# IRIS.net
KiCad netlist of a schematic drawn in EAGLE
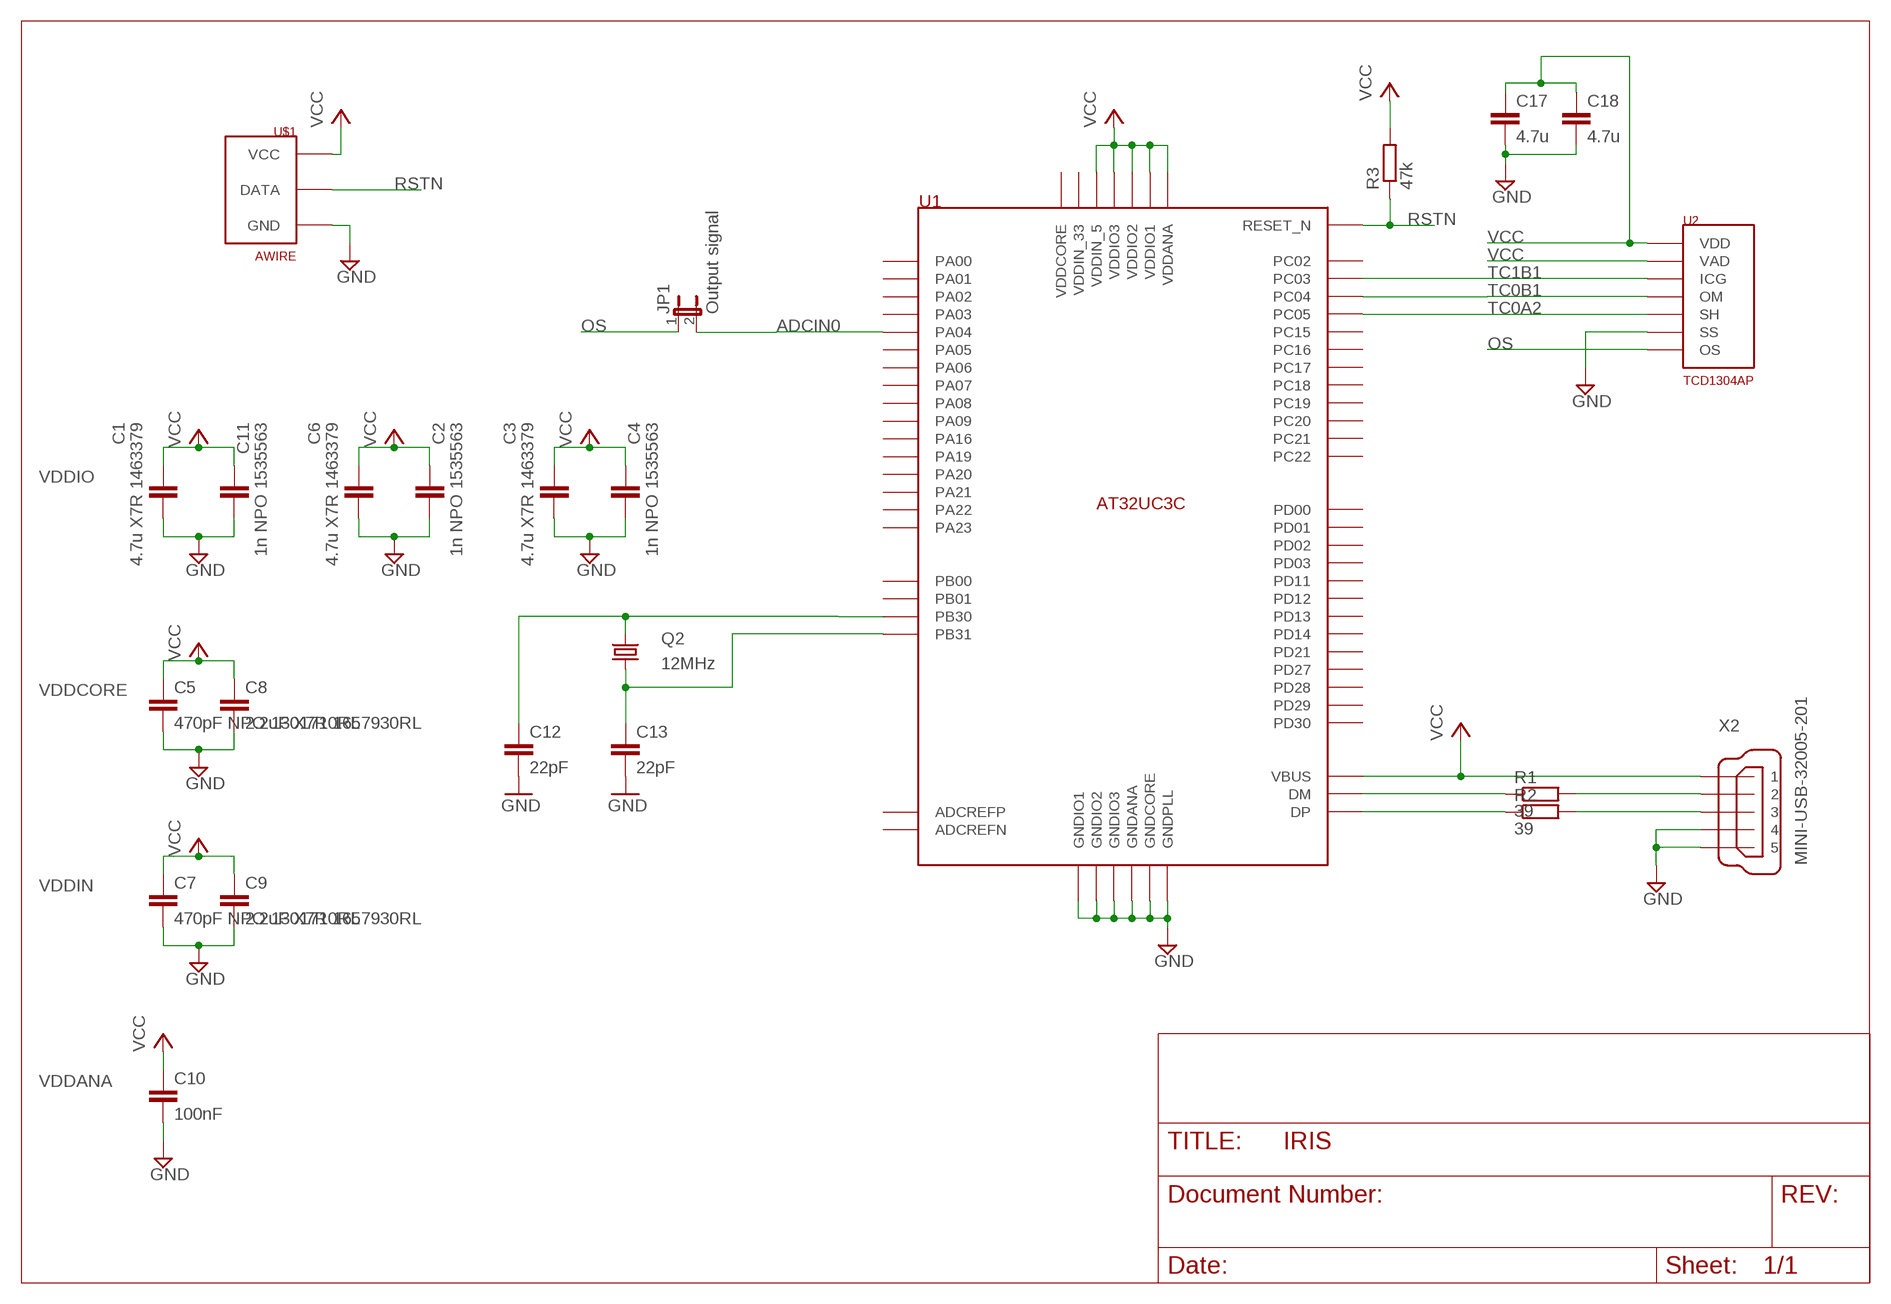
[diagram p0: schematic, sheet 1]

(export (version "E")
  (design (tool "Eeschema 10.0.6"))
  (components
    (comp (ref "C1")
      (value "4.7u X7R 1463379")
      (footprint "eagle-import:C0603")
      (libsource (lib "eagle-import") (part "C-EUC0603"))
    )
    (comp (ref "C2")
      (value "1n NPO 1535563")
      (footprint "eagle-import:C0402")
      (libsource (lib "eagle-import") (part "C-EUC0402"))
    )
    (comp (ref "C3")
      (value "4.7u X7R 1463379")
      (footprint "eagle-import:C0603")
      (libsource (lib "eagle-import") (part "C-EUC0603"))
    )
    (comp (ref "C4")
      (value "1n NPO 1535563")
      (footprint "eagle-import:C0402")
      (libsource (lib "eagle-import") (part "C-EUC0402"))
    )
    (comp (ref "C5")
      (value "470pF NPO 1301710RL")
      (footprint "eagle-import:C0603")
      (libsource (lib "eagle-import") (part "C-EUC0603"))
    )
    (comp (ref "C6")
      (value "4.7u X7R 1463379")
      (footprint "eagle-import:C0603")
      (libsource (lib "eagle-import") (part "C-EUC0603"))
    )
    (comp (ref "C7")
      (value "470pF NPO 1301710RL")
      (footprint "eagle-import:C0603")
      (libsource (lib "eagle-import") (part "C-EUC0603"))
    )
    (comp (ref "C8")
      (value "2.2uF X7R 1657930RL")
      (footprint "eagle-import:C0603")
      (libsource (lib "eagle-import") (part "C-EUC0603"))
    )
    (comp (ref "C9")
      (value "2.2uF X7R 1657930RL")
      (footprint "eagle-import:C0603")
      (libsource (lib "eagle-import") (part "C-EUC0603"))
    )
    (comp (ref "C10")
      (value "100nF")
      (footprint "eagle-import:C0603")
      (libsource (lib "eagle-import") (part "C-EUC0603"))
    )
    (comp (ref "C11")
      (value "1n NPO 1535563")
      (footprint "eagle-import:C0402")
      (libsource (lib "eagle-import") (part "C-EUC0402"))
    )
    (comp (ref "C12")
      (value "22pF")
      (footprint "eagle-import:C0402")
      (libsource (lib "eagle-import") (part "C-EUC0402"))
    )
    (comp (ref "C13")
      (value "22pF")
      (footprint "eagle-import:C0402")
      (libsource (lib "eagle-import") (part "C-EUC0402"))
    )
    (comp (ref "C17")
      (value "4.7u")
      (footprint "eagle-import:C0805")
      (libsource (lib "eagle-import") (part "resistor_C-EUC0805"))
    )
    (comp (ref "C18")
      (value "4.7u")
      (footprint "eagle-import:C0805")
      (libsource (lib "eagle-import") (part "resistor_C-EUC0805"))
    )
    (comp (ref "JP1")
      (value "Output signal")
      (footprint "eagle-import:JP1")
      (libsource (lib "eagle-import") (part "JP1E"))
    )
    (comp (ref "Q2")
      (value "12MHz")
      (footprint "eagle-import:CRYSTAL-SMD-5X3")
      (libsource (lib "eagle-import") (part "CRYSTAL5X3"))
    )
    (comp (ref "R1")
      (value "39")
      (footprint "eagle-import:R0603")
      (libsource (lib "eagle-import") (part "R-EU_R0603"))
    )
    (comp (ref "R2")
      (value "39")
      (footprint "eagle-import:R0603")
      (libsource (lib "eagle-import") (part "R-EU_R0603"))
    )
    (comp (ref "R3")
      (value "47k")
      (footprint "eagle-import:R0603")
      (libsource (lib "eagle-import") (part "R-EU_R0603"))
    )
    (comp (ref "U$1")
      (value "AWIRE")
      (footprint "eagle-import:AWIRE")
      (libsource (lib "eagle-import") (part "AWIRE"))
    )
    (comp (ref "U1")
      (value "AT32UC3C")
      (footprint "eagle-import:TQFP64")
      (libsource (lib "eagle-import") (part "AT32UC3C"))
    )
    (comp (ref "U2")
      (value "TCD1304AP")
      (footprint "eagle-import:TCD1304AP")
      (libsource (lib "eagle-import") (part "TCD1304AP"))
    )
    (comp (ref "X2")
      (value "MINI-USB-32005-201")
      (footprint "eagle-import:32005-201")
      (libsource (lib "eagle-import") (part "MINI-USB-32005-201"))
    )
  )
  (nets
    (net (code "1") (name "/ADCIN0") (class "Default")
      (node (ref "JP1") (pin "2") (pinfunction "2_2") (pintype "passive"))
      (node (ref "U1") (pin "P$7") (pinfunction "PA04_P$7") (pintype "bidirectional"))
    )
    (net (code "2") (name "/OS") (class "Default")
      (node (ref "JP1") (pin "1") (pinfunction "1_1") (pintype "passive"))
      (node (ref "U2") (pin "P$21") (pinfunction "OS_P$21") (pintype "bidirectional"))
    )
    (net (code "3") (name "/RSTN") (class "Default")
      (node (ref "R3") (pin "1") (pinfunction "1_1") (pintype "passive"))
      (node (ref "U$1") (pin "P$2") (pinfunction "DATA_P$2") (pintype "bidirectional"))
      (node (ref "U1") (pin "P$64") (pinfunction "RESET_N_P$64") (pintype "bidirectional"))
    )
    (net (code "4") (name "/TC0A2") (class "Default")
      (node (ref "U1") (pin "P$38") (pinfunction "PC05_P$38") (pintype "bidirectional"))
      (node (ref "U2") (pin "P$5") (pinfunction "SH_P$5") (pintype "bidirectional"))
    )
    (net (code "5") (name "/TC0B1") (class "Default")
      (node (ref "U1") (pin "P$37") (pinfunction "PC04_P$37") (pintype "bidirectional"))
      (node (ref "U2") (pin "P$4") (pinfunction "OM_P$4") (pintype "bidirectional"))
    )
    (net (code "6") (name "/TC1B1") (class "Default")
      (node (ref "U1") (pin "P$34") (pinfunction "PC03_P$34") (pintype "bidirectional"))
      (node (ref "U2") (pin "P$3") (pinfunction "ICG_P$3") (pintype "bidirectional"))
    )
    (net (code "7") (name "GND") (class "Default")
      (node (ref "C1") (pin "2") (pinfunction "2_2") (pintype "passive"))
      (node (ref "C10") (pin "2") (pinfunction "2_2") (pintype "passive"))
      (node (ref "C11") (pin "2") (pinfunction "2_2") (pintype "passive"))
      (node (ref "C12") (pin "2") (pinfunction "2_2") (pintype "passive"))
      (node (ref "C13") (pin "2") (pinfunction "2_2") (pintype "passive"))
      (node (ref "C17") (pin "2") (pinfunction "2_2") (pintype "passive"))
      (node (ref "C18") (pin "2") (pinfunction "2_2") (pintype "passive"))
      (node (ref "C2") (pin "2") (pinfunction "2_2") (pintype "passive"))
      (node (ref "C3") (pin "2") (pinfunction "2_2") (pintype "passive"))
      (node (ref "C4") (pin "2") (pinfunction "2_2") (pintype "passive"))
      (node (ref "C5") (pin "2") (pinfunction "2_2") (pintype "passive"))
      (node (ref "C6") (pin "2") (pinfunction "2_2") (pintype "passive"))
      (node (ref "C7") (pin "2") (pinfunction "2_2") (pintype "passive"))
      (node (ref "C8") (pin "2") (pinfunction "2_2") (pintype "passive"))
      (node (ref "C9") (pin "2") (pinfunction "2_2") (pintype "passive"))
      (node (ref "U$1") (pin "P$3") (pinfunction "GND_P$3") (pintype "bidirectional"))
      (node (ref "U1") (pin "P$17") (pinfunction "GNDANA_P$17") (pintype "bidirectional"))
      (node (ref "U1") (pin "P$26") (pinfunction "GNDPLL_P$26") (pintype "bidirectional"))
      (node (ref "U1") (pin "P$30") (pinfunction "GNDCORE_P$30") (pintype "bidirectional"))
      (node (ref "U1") (pin "P$36") (pinfunction "GNDIO2_P$36") (pintype "bidirectional"))
      (node (ref "U1") (pin "P$52") (pinfunction "GNDIO3_P$52") (pintype "bidirectional"))
      (node (ref "U1") (pin "P$6") (pinfunction "GNDIO1_P$6") (pintype "bidirectional"))
      (node (ref "U2") (pin "P$22") (pinfunction "SS_P$22") (pintype "bidirectional"))
      (node (ref "X2") (pin "4") (pinfunction "4_4") (pintype "passive"))
      (node (ref "X2") (pin "5") (pinfunction "5_5") (pintype "passive"))
    )
    (net (code "8") (name "Net-(Q2-2)") (class "Default")
      (node (ref "C12") (pin "1") (pinfunction "1_1") (pintype "passive"))
      (node (ref "Q2") (pin "3") (pinfunction "2_3") (pintype "passive"))
      (node (ref "U1") (pin "P$31") (pinfunction "PB30_P$31") (pintype "bidirectional"))
    )
    (net (code "9") (name "Net-(R1-Pad2)") (class "Default")
      (node (ref "R1") (pin "2") (pinfunction "2_2") (pintype "passive"))
      (node (ref "X2") (pin "2") (pinfunction "2_2") (pintype "passive"))
    )
    (net (code "10") (name "Net-(R2-Pad2)") (class "Default")
      (node (ref "R2") (pin "2") (pinfunction "2_2") (pintype "passive"))
      (node (ref "X2") (pin "3") (pinfunction "3_3") (pintype "passive"))
    )
    (net (code "11") (name "Net-(U1-DM)") (class "Default")
      (node (ref "R1") (pin "1") (pinfunction "1_1") (pintype "passive"))
      (node (ref "U1") (pin "P$24") (pinfunction "DM_P$24") (pintype "bidirectional"))
    )
    (net (code "12") (name "Net-(U1-DP)") (class "Default")
      (node (ref "R2") (pin "1") (pinfunction "1_1") (pintype "passive"))
      (node (ref "U1") (pin "P$25") (pinfunction "DP_P$25") (pintype "bidirectional"))
    )
    (net (code "13") (name "Net-(U1-PB31)") (class "Default")
      (node (ref "C13") (pin "1") (pinfunction "1_1") (pintype "passive"))
      (node (ref "Q2") (pin "1") (pinfunction "1_1") (pintype "passive"))
      (node (ref "U1") (pin "P$32") (pinfunction "PB31_P$32") (pintype "bidirectional"))
    )
    (net (code "14") (name "VCC") (class "Default")
      (node (ref "C1") (pin "1") (pinfunction "1_1") (pintype "passive"))
      (node (ref "C10") (pin "1") (pinfunction "1_1") (pintype "passive"))
      (node (ref "C11") (pin "1") (pinfunction "1_1") (pintype "passive"))
      (node (ref "C17") (pin "1") (pinfunction "1_1") (pintype "passive"))
      (node (ref "C18") (pin "1") (pinfunction "1_1") (pintype "passive"))
      (node (ref "C2") (pin "1") (pinfunction "1_1") (pintype "passive"))
      (node (ref "C3") (pin "1") (pinfunction "1_1") (pintype "passive"))
      (node (ref "C4") (pin "1") (pinfunction "1_1") (pintype "passive"))
      (node (ref "C5") (pin "1") (pinfunction "1_1") (pintype "passive"))
      (node (ref "C6") (pin "1") (pinfunction "1_1") (pintype "passive"))
      (node (ref "C7") (pin "1") (pinfunction "1_1") (pintype "passive"))
      (node (ref "C8") (pin "1") (pinfunction "1_1") (pintype "passive"))
      (node (ref "C9") (pin "1") (pinfunction "1_1") (pintype "passive"))
      (node (ref "R3") (pin "2") (pinfunction "2_2") (pintype "passive"))
      (node (ref "U$1") (pin "P$1") (pinfunction "VCC_P$1") (pintype "bidirectional"))
      (node (ref "U1") (pin "P$18") (pinfunction "VDDANA_P$18") (pintype "bidirectional"))
      (node (ref "U1") (pin "P$23") (pinfunction "VBUS_P$23") (pintype "bidirectional"))
      (node (ref "U1") (pin "P$27") (pinfunction "VDDIN_5_P$27") (pintype "bidirectional"))
      (node (ref "U1") (pin "P$35") (pinfunction "VDDIO2_P$35") (pintype "bidirectional"))
      (node (ref "U1") (pin "P$5") (pinfunction "VDDIO1_P$5") (pintype "bidirectional"))
      (node (ref "U1") (pin "P$51") (pinfunction "VDDIO3_P$51") (pintype "bidirectional"))
      (node (ref "U2") (pin "P$1") (pinfunction "VDD_P$1") (pintype "bidirectional"))
      (node (ref "U2") (pin "P$2") (pinfunction "VAD_P$2") (pintype "bidirectional"))
      (node (ref "X2") (pin "1") (pinfunction "1_1") (pintype "passive"))
    )
    (net (code "15") (name "unconnected-(U1-ADCREFN-PadP$15)") (class "Default")
      (node (ref "U1") (pin "P$15") (pinfunction "ADCREFN_P$15") (pintype "bidirectional"))
    )
    (net (code "16") (name "unconnected-(U1-ADCREFP-PadP$14)") (class "Default")
      (node (ref "U1") (pin "P$14") (pinfunction "ADCREFP_P$14") (pintype "bidirectional"))
    )
    (net (code "17") (name "unconnected-(U1-PA00-PadP$1)") (class "Default")
      (node (ref "U1") (pin "P$1") (pinfunction "PA00_P$1") (pintype "bidirectional"))
    )
    (net (code "18") (name "unconnected-(U1-PA01-PadP$2)") (class "Default")
      (node (ref "U1") (pin "P$2") (pinfunction "PA01_P$2") (pintype "bidirectional"))
    )
    (net (code "19") (name "unconnected-(U1-PA02-PadP$3)") (class "Default")
      (node (ref "U1") (pin "P$3") (pinfunction "PA02_P$3") (pintype "bidirectional"))
    )
    (net (code "20") (name "unconnected-(U1-PA03-PadP$4)") (class "Default")
      (node (ref "U1") (pin "P$4") (pinfunction "PA03_P$4") (pintype "bidirectional"))
    )
    (net (code "21") (name "unconnected-(U1-PA05-PadP$8)") (class "Default")
      (node (ref "U1") (pin "P$8") (pinfunction "PA05_P$8") (pintype "bidirectional"))
    )
    (net (code "22") (name "unconnected-(U1-PA06-PadP$9)") (class "Default")
      (node (ref "U1") (pin "P$9") (pinfunction "PA06_P$9") (pintype "bidirectional"))
    )
    (net (code "23") (name "unconnected-(U1-PA07-PadP$10)") (class "Default")
      (node (ref "U1") (pin "P$10") (pinfunction "PA07_P$10") (pintype "bidirectional"))
    )
    (net (code "24") (name "unconnected-(U1-PA08-PadP$11)") (class "Default")
      (node (ref "U1") (pin "P$11") (pinfunction "PA08_P$11") (pintype "bidirectional"))
    )
    (net (code "25") (name "unconnected-(U1-PA09-PadP$12)") (class "Default")
      (node (ref "U1") (pin "P$12") (pinfunction "PA09_P$12") (pintype "bidirectional"))
    )
    (net (code "26") (name "unconnected-(U1-PA16-PadP$13)") (class "Default")
      (node (ref "U1") (pin "P$13") (pinfunction "PA16_P$13") (pintype "bidirectional"))
    )
    (net (code "27") (name "unconnected-(U1-PA19-PadP$16)") (class "Default")
      (node (ref "U1") (pin "P$16") (pinfunction "PA19_P$16") (pintype "bidirectional"))
    )
    (net (code "28") (name "unconnected-(U1-PA20-PadP$19)") (class "Default")
      (node (ref "U1") (pin "P$19") (pinfunction "PA20_P$19") (pintype "bidirectional"))
    )
    (net (code "29") (name "unconnected-(U1-PA21-PadP$20)") (class "Default")
      (node (ref "U1") (pin "P$20") (pinfunction "PA21_P$20") (pintype "bidirectional"))
    )
    (net (code "30") (name "unconnected-(U1-PA22-PadP$21)") (class "Default")
      (node (ref "U1") (pin "P$21") (pinfunction "PA22_P$21") (pintype "bidirectional"))
    )
    (net (code "31") (name "unconnected-(U1-PA23-PadP$22)") (class "Default")
      (node (ref "U1") (pin "P$22") (pinfunction "PA23_P$22") (pintype "bidirectional"))
    )
    (net (code "32") (name "unconnected-(U1-PB00-PadP$62)") (class "Default")
      (node (ref "U1") (pin "P$62") (pinfunction "PB00_P$62") (pintype "bidirectional"))
    )
    (net (code "33") (name "unconnected-(U1-PB01-PadP$63)") (class "Default")
      (node (ref "U1") (pin "P$63") (pinfunction "PB01_P$63") (pintype "bidirectional"))
    )
    (net (code "34") (name "unconnected-(U1-PC02-PadP$33)") (class "Default")
      (node (ref "U1") (pin "P$33") (pinfunction "PC02_P$33") (pintype "bidirectional"))
    )
    (net (code "35") (name "unconnected-(U1-PC15-PadP$39)") (class "Default")
      (node (ref "U1") (pin "P$39") (pinfunction "PC15_P$39") (pintype "bidirectional"))
    )
    (net (code "36") (name "unconnected-(U1-PC16-PadP$40)") (class "Default")
      (node (ref "U1") (pin "P$40") (pinfunction "PC16_P$40") (pintype "bidirectional"))
    )
    (net (code "37") (name "unconnected-(U1-PC17-PadP$41)") (class "Default")
      (node (ref "U1") (pin "P$41") (pinfunction "PC17_P$41") (pintype "bidirectional"))
    )
    (net (code "38") (name "unconnected-(U1-PC18-PadP$42)") (class "Default")
      (node (ref "U1") (pin "P$42") (pinfunction "PC18_P$42") (pintype "bidirectional"))
    )
    (net (code "39") (name "unconnected-(U1-PC19-PadP$43)") (class "Default")
      (node (ref "U1") (pin "P$43") (pinfunction "PC19_P$43") (pintype "bidirectional"))
    )
    (net (code "40") (name "unconnected-(U1-PC20-PadP$44)") (class "Default")
      (node (ref "U1") (pin "P$44") (pinfunction "PC20_P$44") (pintype "bidirectional"))
    )
    (net (code "41") (name "unconnected-(U1-PC21-PadP$45)") (class "Default")
      (node (ref "U1") (pin "P$45") (pinfunction "PC21_P$45") (pintype "bidirectional"))
    )
    (net (code "42") (name "unconnected-(U1-PC22-PadP$46)") (class "Default")
      (node (ref "U1") (pin "P$46") (pinfunction "PC22_P$46") (pintype "bidirectional"))
    )
    (net (code "43") (name "unconnected-(U1-PD00-PadP$47)") (class "Default")
      (node (ref "U1") (pin "P$47") (pinfunction "PD00_P$47") (pintype "bidirectional"))
    )
    (net (code "44") (name "unconnected-(U1-PD01-PadP$48)") (class "Default")
      (node (ref "U1") (pin "P$48") (pinfunction "PD01_P$48") (pintype "bidirectional"))
    )
    (net (code "45") (name "unconnected-(U1-PD02-PadP$49)") (class "Default")
      (node (ref "U1") (pin "P$49") (pinfunction "PD02_P$49") (pintype "bidirectional"))
    )
    (net (code "46") (name "unconnected-(U1-PD03-PadP$50)") (class "Default")
      (node (ref "U1") (pin "P$50") (pinfunction "PD03_P$50") (pintype "bidirectional"))
    )
    (net (code "47") (name "unconnected-(U1-PD11-PadP$53)") (class "Default")
      (node (ref "U1") (pin "P$53") (pinfunction "PD11_P$53") (pintype "bidirectional"))
    )
    (net (code "48") (name "unconnected-(U1-PD12-PadP$54)") (class "Default")
      (node (ref "U1") (pin "P$54") (pinfunction "PD12_P$54") (pintype "bidirectional"))
    )
    (net (code "49") (name "unconnected-(U1-PD13-PadP$55)") (class "Default")
      (node (ref "U1") (pin "P$55") (pinfunction "PD13_P$55") (pintype "bidirectional"))
    )
    (net (code "50") (name "unconnected-(U1-PD14-PadP$56)") (class "Default")
      (node (ref "U1") (pin "P$56") (pinfunction "PD14_P$56") (pintype "bidirectional"))
    )
    (net (code "51") (name "unconnected-(U1-PD21-PadP$57)") (class "Default")
      (node (ref "U1") (pin "P$57") (pinfunction "PD21_P$57") (pintype "bidirectional"))
    )
    (net (code "52") (name "unconnected-(U1-PD27-PadP$58)") (class "Default")
      (node (ref "U1") (pin "P$58") (pinfunction "PD27_P$58") (pintype "bidirectional"))
    )
    (net (code "53") (name "unconnected-(U1-PD28-PadP$59)") (class "Default")
      (node (ref "U1") (pin "P$59") (pinfunction "PD28_P$59") (pintype "bidirectional"))
    )
    (net (code "54") (name "unconnected-(U1-PD29-PadP$60)") (class "Default")
      (node (ref "U1") (pin "P$60") (pinfunction "PD29_P$60") (pintype "bidirectional"))
    )
    (net (code "55") (name "unconnected-(U1-PD30-PadP$61)") (class "Default")
      (node (ref "U1") (pin "P$61") (pinfunction "PD30_P$61") (pintype "bidirectional"))
    )
    (net (code "56") (name "unconnected-(U1-VDDCORE-PadP$29)") (class "Default")
      (node (ref "U1") (pin "P$29") (pinfunction "VDDCORE_P$29") (pintype "bidirectional"))
    )
    (net (code "57") (name "unconnected-(U1-VDDIN_33-PadP$28)") (class "Default")
      (node (ref "U1") (pin "P$28") (pinfunction "VDDIN_33_P$28") (pintype "bidirectional"))
    )
  )
)
